# ArduinoUnoShield.net
KiCad netlist of a schematic drawn in Altium Designer
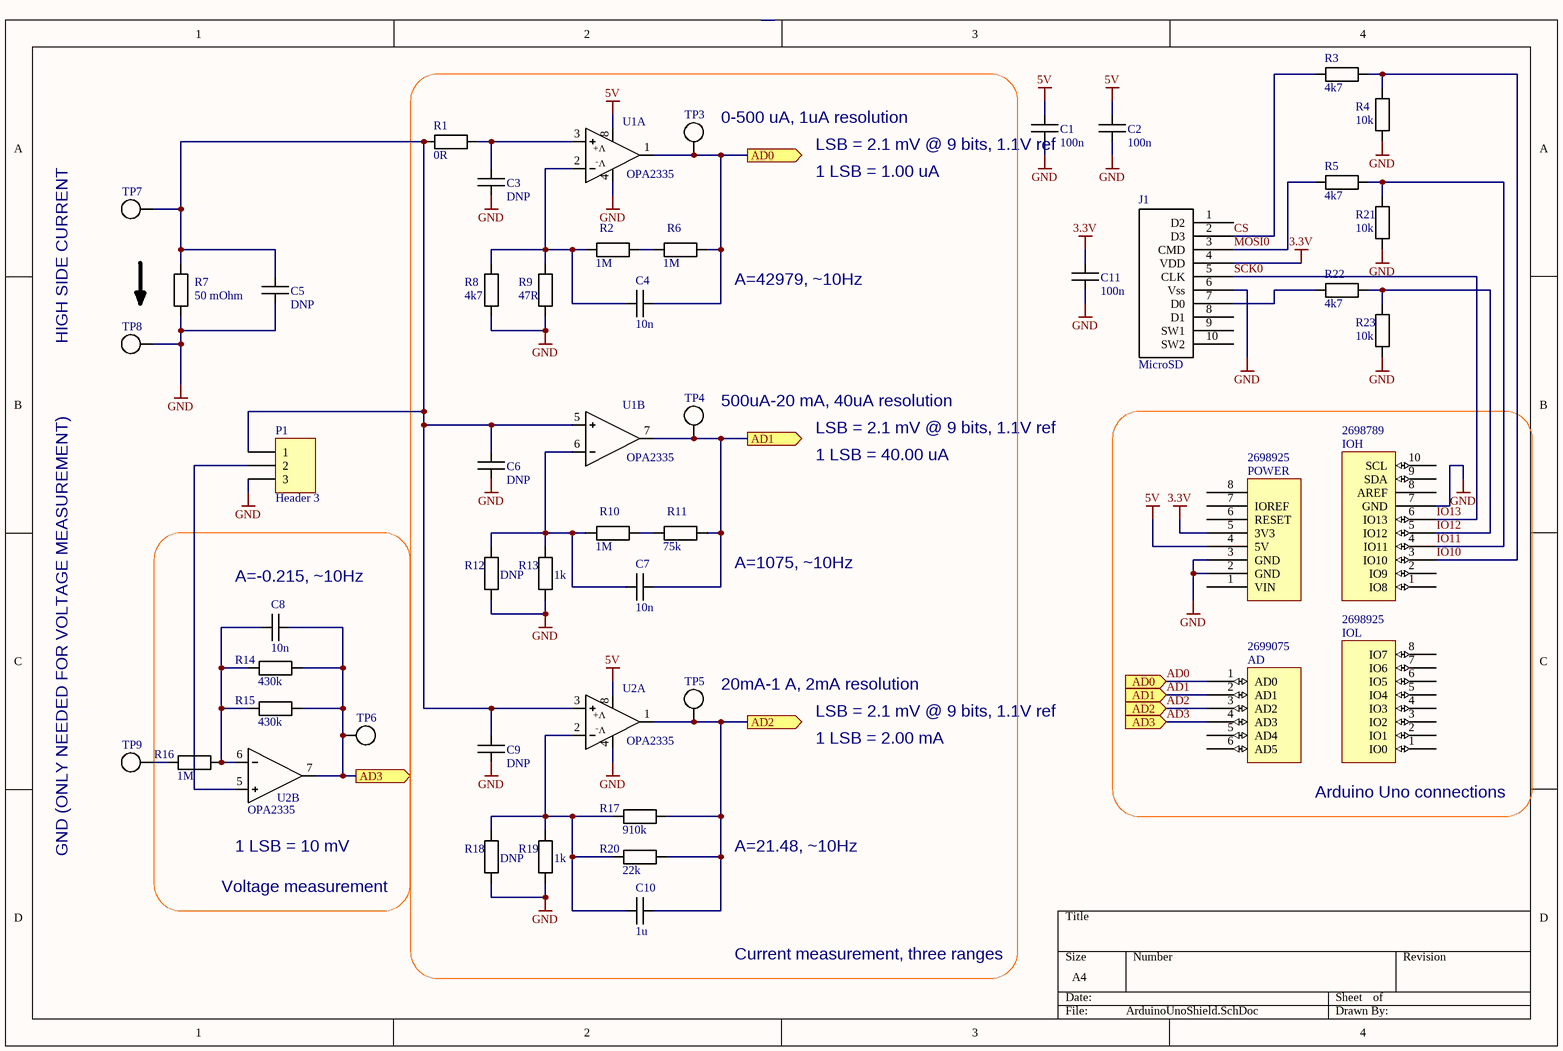
[diagram p0: ArduinoUnoShield.SchDoc]

(export (version "E")
  (design (tool "Eeschema 10.0.6"))
  (components
    (comp (ref "AD")
      (value "AD")
      (footprint "Header:Header 6x1 8.5mm")
      (fields (field (name "SUPPLIER PART NUMBER 4") "2699075"))
      (libsource (lib "Header") (part "AD"))
    )
    (comp (ref "C1")
      (value "100n")
      (footprint "0603CAP")
      (description "Ceramic Capacitor SMD 0603")
      (fields (field (name "Comment") "CAP0603"))
      (libsource (lib "PARTS") (part "185"))
    )
    (comp (ref "C2")
      (value "100n")
      (footprint "0603CAP")
      (description "Ceramic Capacitor SMD 0603")
      (fields (field (name "Comment") "CAP0603"))
      (libsource (lib "PARTS") (part "185"))
    )
    (comp (ref "C3")
      (value "DNP")
      (footprint "0603CAP")
      (description "Ceramic Capacitor SMD 0603")
      (fields (field (name "Comment") "CAP0603"))
      (libsource (lib "PARTS") (part "185"))
    )
    (comp (ref "C4")
      (value "10n")
      (footprint "0603CAP")
      (description "Ceramic Capacitor SMD 0603")
      (fields (field (name "Comment") "CAP0603"))
      (libsource (lib "PARTS") (part "185"))
    )
    (comp (ref "C5")
      (value "DNP")
      (footprint "0603CAP")
      (description "Ceramic Capacitor SMD 0603")
      (fields (field (name "Comment") "CAP0603"))
      (libsource (lib "PARTS") (part "185"))
    )
    (comp (ref "C6")
      (value "DNP")
      (footprint "0603CAP")
      (description "Ceramic Capacitor SMD 0603")
      (fields (field (name "Comment") "CAP0603"))
      (libsource (lib "PARTS") (part "185"))
    )
    (comp (ref "C7")
      (value "10n")
      (footprint "0603CAP")
      (description "Ceramic Capacitor SMD 0603")
      (fields (field (name "Comment") "CAP0603"))
      (libsource (lib "PARTS") (part "185"))
    )
    (comp (ref "C8")
      (value "10n")
      (footprint "0603CAP")
      (description "Ceramic Capacitor SMD 0603")
      (fields (field (name "Comment") "CAP0603"))
      (libsource (lib "PARTS") (part "185"))
    )
    (comp (ref "C9")
      (value "DNP")
      (footprint "0603CAP")
      (description "Ceramic Capacitor SMD 0603")
      (fields (field (name "Comment") "CAP0603"))
      (libsource (lib "PARTS") (part "185"))
    )
    (comp (ref "C10")
      (value "1u")
      (footprint "0603CAP")
      (description "Ceramic Capacitor SMD 0603")
      (fields (field (name "Comment") "CAP0603"))
      (libsource (lib "PARTS") (part "185"))
    )
    (comp (ref "C11")
      (value "100n")
      (footprint "0603CAP")
      (description "Ceramic Capacitor SMD 0603")
      (fields (field (name "Comment") "CAP0603"))
      (libsource (lib "PARTS") (part "185"))
    )
    (comp (ref "IOH")
      (value "IOH")
      (footprint "Header:Header 10x1 8.5mm")
      (fields (field (name "SUPPLIER PART NUMBER 3") "2698789"))
      (libsource (lib "Header") (part "IOH"))
    )
    (comp (ref "IOL")
      (value "IOL")
      (footprint "Header 8x1 8.5mm")
      (fields (field (name "SUPPLIER PART NUMBER 4") "2698925"))
      (libsource (lib "Header") (part "IOL"))
    )
    (comp (ref "J1") (value "MicroSD") (footprint "micro SD") (libsource (lib "moja") (part "MicroSD")))
    (comp (ref "P1")
      (value "Header 3")
      (footprint "HDR1X3")
      (description "Header, 3-Pin")
      (fields (field (name "PUBLISHER") "Altium Limited"))
      (libsource (lib "Miscellaneous Connectors") (part "Header 3"))
    )
    (comp (ref "POWER")
      (value "POWER_UNO")
      (footprint "Header 8x1 8.5mm")
      (fields (field (name "SUPPLIER PART NUMBER 4") "2698925"))
      (libsource (lib "Header") (part "POWER_UNO"))
    )
    (comp (ref "R1")
      (value "0R")
      (footprint "RES0603")
      (description "Resistor 0603 SMD")
      (fields (field (name "Comment") "RES_STANDARD"))
      (libsource (lib "PARTS") (part "276"))
    )
    (comp (ref "R2")
      (value "1M")
      (footprint "RES0603")
      (description "Resistor 0603 SMD")
      (fields (field (name "Comment") "RES_STANDARD"))
      (libsource (lib "PARTS") (part "276"))
    )
    (comp (ref "R3")
      (value "4k7")
      (footprint "RES0603")
      (description "Resistor 0603 SMD")
      (fields (field (name "Comment") "RES_STANDARD"))
      (libsource (lib "PARTS") (part "276"))
    )
    (comp (ref "R4")
      (value "10k")
      (footprint "RES0603")
      (description "Resistor 0603 SMD")
      (fields (field (name "Comment") "RES_STANDARD"))
      (libsource (lib "PARTS") (part "276"))
    )
    (comp (ref "R5")
      (value "4k7")
      (footprint "RES0603")
      (description "Resistor 0603 SMD")
      (fields (field (name "Comment") "RES_STANDARD"))
      (libsource (lib "PARTS") (part "276"))
    )
    (comp (ref "R6")
      (value "1M")
      (footprint "RES0603")
      (description "Resistor 0603 SMD")
      (fields (field (name "Comment") "RES_STANDARD"))
      (libsource (lib "PARTS") (part "276"))
    )
    (comp (ref "R7")
      (value "50 mOhm")
      (footprint "RES0603")
      (description "Resistor 0603 SMD")
      (fields (field (name "Comment") "RES_STANDARD"))
      (libsource (lib "PARTS") (part "276"))
    )
    (comp (ref "R8")
      (value "4k7")
      (footprint "RES0603")
      (description "Resistor 0603 SMD")
      (fields (field (name "Comment") "RES_STANDARD"))
      (libsource (lib "PARTS") (part "276"))
    )
    (comp (ref "R9")
      (value "47R")
      (footprint "RES0603")
      (description "Resistor 0603 SMD")
      (fields (field (name "Comment") "RES_STANDARD"))
      (libsource (lib "PARTS") (part "276"))
    )
    (comp (ref "R10")
      (value "1M")
      (footprint "RES0603")
      (description "Resistor 0603 SMD")
      (fields (field (name "Comment") "RES_STANDARD"))
      (libsource (lib "PARTS") (part "276"))
    )
    (comp (ref "R11")
      (value "75k")
      (footprint "RES0603")
      (description "Resistor 0603 SMD")
      (fields (field (name "Comment") "RES_STANDARD"))
      (libsource (lib "PARTS") (part "276"))
    )
    (comp (ref "R12")
      (value "DNP")
      (footprint "RES0603")
      (description "Resistor 0603 SMD")
      (fields (field (name "Comment") "RES_STANDARD"))
      (libsource (lib "PARTS") (part "276"))
    )
    (comp (ref "R13")
      (value "1k")
      (footprint "RES0603")
      (description "Resistor 0603 SMD")
      (fields (field (name "Comment") "RES_STANDARD"))
      (libsource (lib "PARTS") (part "276"))
    )
    (comp (ref "R14")
      (value "430k")
      (footprint "RES0603")
      (description "Resistor 0603 SMD")
      (fields (field (name "Comment") "RES_STANDARD"))
      (libsource (lib "PARTS") (part "276"))
    )
    (comp (ref "R15")
      (value "430k")
      (footprint "RES0603")
      (description "Resistor 0603 SMD")
      (fields (field (name "Comment") "RES_STANDARD"))
      (libsource (lib "PARTS") (part "276"))
    )
    (comp (ref "R16")
      (value "1M")
      (footprint "RES0603")
      (description "Resistor 0603 SMD")
      (fields (field (name "Comment") "RES_STANDARD"))
      (libsource (lib "PARTS") (part "276"))
    )
    (comp (ref "R17")
      (value "910k")
      (footprint "RES0603")
      (description "Resistor 0603 SMD")
      (fields (field (name "Comment") "RES_STANDARD"))
      (libsource (lib "PARTS") (part "276"))
    )
    (comp (ref "R18")
      (value "DNP")
      (footprint "RES0603")
      (description "Resistor 0603 SMD")
      (fields (field (name "Comment") "RES_STANDARD"))
      (libsource (lib "PARTS") (part "276"))
    )
    (comp (ref "R19")
      (value "1k")
      (footprint "RES0603")
      (description "Resistor 0603 SMD")
      (fields (field (name "Comment") "RES_STANDARD"))
      (libsource (lib "PARTS") (part "276"))
    )
    (comp (ref "R20")
      (value "22k")
      (footprint "RES0603")
      (description "Resistor 0603 SMD")
      (fields (field (name "Comment") "RES_STANDARD"))
      (libsource (lib "PARTS") (part "276"))
    )
    (comp (ref "R21")
      (value "10k")
      (footprint "RES0603")
      (description "Resistor 0603 SMD")
      (fields (field (name "Comment") "RES_STANDARD"))
      (libsource (lib "PARTS") (part "276"))
    )
    (comp (ref "R22")
      (value "4k7")
      (footprint "RES0603")
      (description "Resistor 0603 SMD")
      (fields (field (name "Comment") "RES_STANDARD"))
      (libsource (lib "PARTS") (part "276"))
    )
    (comp (ref "R23")
      (value "10k")
      (footprint "RES0603")
      (description "Resistor 0603 SMD")
      (fields (field (name "Comment") "RES_STANDARD"))
      (libsource (lib "PARTS") (part "276"))
    )
    (comp (ref "TP3")
      (value "TESTPOINT_1.6MM")
      (footprint "TESTPOINT_1.6MM")
      (description "Testpoint")
      (libsource (lib "PARTS") (part "203"))
    )
    (comp (ref "TP4")
      (value "TESTPOINT_1.6MM")
      (footprint "TESTPOINT_1.6MM")
      (description "Testpoint")
      (libsource (lib "PARTS") (part "203"))
    )
    (comp (ref "TP5")
      (value "TESTPOINT_1.6MM")
      (footprint "TESTPOINT_1.6MM")
      (description "Testpoint")
      (libsource (lib "PARTS") (part "203"))
    )
    (comp (ref "TP6")
      (value "TESTPOINT_1.6MM")
      (footprint "TESTPOINT_1.6MM")
      (description "Testpoint")
      (libsource (lib "PARTS") (part "203"))
    )
    (comp (ref "TP7")
      (value "TESTPOINT_1.6MM")
      (footprint "TESTPOINT_1.6MM")
      (description "Testpoint")
      (libsource (lib "PARTS") (part "203"))
    )
    (comp (ref "TP8")
      (value "TESTPOINT_1.6MM")
      (footprint "TESTPOINT_1.6MM")
      (description "Testpoint")
      (libsource (lib "PARTS") (part "203"))
    )
    (comp (ref "TP9")
      (value "TESTPOINT_1.6MM")
      (footprint "TESTPOINT_1.6MM")
      (description "Testpoint")
      (libsource (lib "PARTS") (part "203"))
    )
    (comp (ref "U1")
      (value "OPA2335")
      (footprint "SO8")
      (description "Dual and Quad 75 MHz GBW Rail-to-Rail I/O Operational")
      (libsource (lib "PARTS") (part "104"))
    )
    (comp (ref "U2")
      (value "OPA2335")
      (footprint "SO8")
      (description "Dual and Quad 75 MHz GBW Rail-to-Rail I/O Operational")
      (libsource (lib "PARTS") (part "104"))
    )
  )
  (nets
    (net (code "1") (name "/AD0") (class "Default")
      (node (ref "AD") (pin "1") (pinfunction "AD0_1") (pintype "bidirectional"))
      (node (ref "C4") (pin "2") (pinfunction "2_2") (pintype "passive"))
      (node (ref "R6") (pin "1") (pinfunction "1_1") (pintype "passive"))
      (node (ref "TP3") (pin "1") (pinfunction "1_1") (pintype "passive"))
      (node (ref "U1") (pin "1") (pinfunction "Output_A_1") (pintype "passive"))
    )
    (net (code "2") (name "/AD1") (class "Default")
      (node (ref "AD") (pin "2") (pinfunction "AD1_2") (pintype "bidirectional"))
      (node (ref "C7") (pin "2") (pinfunction "2_2") (pintype "passive"))
      (node (ref "R11") (pin "1") (pinfunction "1_1") (pintype "passive"))
      (node (ref "TP4") (pin "1") (pinfunction "1_1") (pintype "passive"))
      (node (ref "U1") (pin "7") (pinfunction "OUT_B_7") (pintype "passive"))
    )
    (net (code "3") (name "/AD2") (class "Default")
      (node (ref "AD") (pin "3") (pinfunction "AD2_3") (pintype "bidirectional"))
      (node (ref "C10") (pin "2") (pinfunction "2_2") (pintype "passive"))
      (node (ref "R17") (pin "1") (pinfunction "1_1") (pintype "passive"))
      (node (ref "R20") (pin "1") (pinfunction "1_1") (pintype "passive"))
      (node (ref "TP5") (pin "1") (pinfunction "1_1") (pintype "passive"))
      (node (ref "U2") (pin "1") (pinfunction "Output_A_1") (pintype "passive"))
    )
    (net (code "4") (name "/AD3") (class "Default")
      (node (ref "AD") (pin "4") (pinfunction "AD3_4") (pintype "bidirectional"))
      (node (ref "C8") (pin "2") (pinfunction "2_2") (pintype "passive"))
      (node (ref "R14") (pin "1") (pinfunction "1_1") (pintype "passive"))
      (node (ref "R15") (pin "1") (pinfunction "1_1") (pintype "passive"))
      (node (ref "TP6") (pin "1") (pinfunction "1_1") (pintype "passive"))
      (node (ref "U2") (pin "7") (pinfunction "OUT_B_7") (pintype "passive"))
    )
    (net (code "5") (name "/CS") (class "Default")
      (node (ref "J1") (pin "2") (pinfunction "D3_2") (pintype "passive"))
      (node (ref "R3") (pin "2") (pinfunction "2_2") (pintype "passive"))
    )
    (net (code "6") (name "/IO10") (class "Default")
      (node (ref "IOH") (pin "3") (pinfunction "IO10_3") (pintype "bidirectional"))
      (node (ref "R3") (pin "1") (pinfunction "1_1") (pintype "passive"))
      (node (ref "R4") (pin "2") (pinfunction "2_2") (pintype "passive"))
    )
    (net (code "7") (name "/IO11") (class "Default")
      (node (ref "IOH") (pin "4") (pinfunction "IO11_4") (pintype "bidirectional"))
      (node (ref "R21") (pin "2") (pinfunction "2_2") (pintype "passive"))
      (node (ref "R5") (pin "1") (pinfunction "1_1") (pintype "passive"))
    )
    (net (code "8") (name "/IO12") (class "Default")
      (node (ref "IOH") (pin "5") (pinfunction "IO12_5") (pintype "bidirectional"))
      (node (ref "R22") (pin "1") (pinfunction "1_1") (pintype "passive"))
      (node (ref "R23") (pin "2") (pinfunction "2_2") (pintype "passive"))
    )
    (net (code "9") (name "/IO13") (class "Default")
      (node (ref "IOH") (pin "6") (pinfunction "IO13_6") (pintype "bidirectional"))
      (node (ref "J1") (pin "5") (pinfunction "CLK_5") (pintype "passive"))
    )
    (net (code "10") (name "/MOSI0") (class "Default")
      (node (ref "J1") (pin "3") (pinfunction "CMD_3") (pintype "passive"))
      (node (ref "R5") (pin "2") (pinfunction "2_2") (pintype "passive"))
    )
    (net (code "11") (name "3.3V") (class "Default")
      (node (ref "C11") (pin "2") (pinfunction "2_2") (pintype "passive"))
      (node (ref "J1") (pin "4") (pinfunction "VDD_4") (pintype "passive"))
      (node (ref "POWER") (pin "5") (pinfunction "3V3_5") (pintype "power_in"))
    )
    (net (code "12") (name "5V") (class "Default")
      (node (ref "C1") (pin "2") (pinfunction "2_2") (pintype "passive"))
      (node (ref "C2") (pin "2") (pinfunction "2_2") (pintype "passive"))
      (node (ref "POWER") (pin "4") (pinfunction "5V_4") (pintype "power_in"))
      (node (ref "U1") (pin "8") (pinfunction "V+_8") (pintype "passive"))
      (node (ref "U2") (pin "8") (pinfunction "V+_8") (pintype "passive"))
    )
    (net (code "13") (name "GND") (class "Default")
      (node (ref "C1") (pin "1") (pinfunction "1_1") (pintype "passive"))
      (node (ref "C11") (pin "1") (pinfunction "1_1") (pintype "passive"))
      (node (ref "C2") (pin "1") (pinfunction "1_1") (pintype "passive"))
      (node (ref "C3") (pin "2") (pinfunction "2_2") (pintype "passive"))
      (node (ref "C5") (pin "2") (pinfunction "2_2") (pintype "passive"))
      (node (ref "C6") (pin "2") (pinfunction "2_2") (pintype "passive"))
      (node (ref "C9") (pin "2") (pinfunction "2_2") (pintype "passive"))
      (node (ref "IOH") (pin "7") (pinfunction "GND_7") (pintype "power_in"))
      (node (ref "J1") (pin "6") (pinfunction "Vss_6") (pintype "passive"))
      (node (ref "P1") (pin "3") (pinfunction "3_3") (pintype "passive"))
      (node (ref "POWER") (pin "2") (pinfunction "GND_2") (pintype "power_in"))
      (node (ref "POWER") (pin "3") (pinfunction "GND_3") (pintype "power_in"))
      (node (ref "R12") (pin "1") (pinfunction "1_1") (pintype "passive"))
      (node (ref "R13") (pin "1") (pinfunction "1_1") (pintype "passive"))
      (node (ref "R18") (pin "1") (pinfunction "1_1") (pintype "passive"))
      (node (ref "R19") (pin "1") (pinfunction "1_1") (pintype "passive"))
      (node (ref "R21") (pin "1") (pinfunction "1_1") (pintype "passive"))
      (node (ref "R23") (pin "1") (pinfunction "1_1") (pintype "passive"))
      (node (ref "R4") (pin "1") (pinfunction "1_1") (pintype "passive"))
      (node (ref "R7") (pin "1") (pinfunction "1_1") (pintype "passive"))
      (node (ref "R8") (pin "1") (pinfunction "1_1") (pintype "passive"))
      (node (ref "R9") (pin "1") (pinfunction "1_1") (pintype "passive"))
      (node (ref "TP8") (pin "1") (pinfunction "1_1") (pintype "passive"))
      (node (ref "U1") (pin "4") (pinfunction "V-_4") (pintype "passive"))
      (node (ref "U2") (pin "4") (pinfunction "V-_4") (pintype "passive"))
    )
    (net (code "14") (name "Net-(J1-D0)") (class "Default")
      (node (ref "J1") (pin "7") (pinfunction "D0_7") (pintype "passive"))
      (node (ref "R22") (pin "2") (pinfunction "2_2") (pintype "passive"))
    )
    (net (code "15") (name "Net-(R2-Pad1)") (class "Default")
      (node (ref "R2") (pin "1") (pinfunction "1_1") (pintype "passive"))
      (node (ref "R6") (pin "2") (pinfunction "2_2") (pintype "passive"))
    )
    (net (code "16") (name "Net-(R10-Pad1)") (class "Default")
      (node (ref "R10") (pin "1") (pinfunction "1_1") (pintype "passive"))
      (node (ref "R11") (pin "2") (pinfunction "2_2") (pintype "passive"))
    )
    (net (code "17") (name "Net-(R16-Pad2)") (class "Default")
      (node (ref "R16") (pin "2") (pinfunction "2_2") (pintype "passive"))
      (node (ref "TP9") (pin "1") (pinfunction "1_1") (pintype "passive"))
    )
    (net (code "18") (name "Net-(U1A-Inv_IN_A)") (class "Default")
      (node (ref "C4") (pin "1") (pinfunction "1_1") (pintype "passive"))
      (node (ref "R2") (pin "2") (pinfunction "2_2") (pintype "passive"))
      (node (ref "R8") (pin "2") (pinfunction "2_2") (pintype "passive"))
      (node (ref "R9") (pin "2") (pinfunction "2_2") (pintype "passive"))
      (node (ref "U1") (pin "2") (pinfunction "Inv_IN_A_2") (pintype "passive"))
    )
    (net (code "19") (name "Net-(U1A-Non-inv_IN_A)") (class "Default")
      (node (ref "C3") (pin "1") (pinfunction "1_1") (pintype "passive"))
      (node (ref "R1") (pin "2") (pinfunction "2_2") (pintype "passive"))
      (node (ref "U1") (pin "3") (pinfunction "Non-inv_IN_A_3") (pintype "passive"))
    )
    (net (code "20") (name "Net-(U1B-Inv_IN_B)") (class "Default")
      (node (ref "C7") (pin "1") (pinfunction "1_1") (pintype "passive"))
      (node (ref "R10") (pin "2") (pinfunction "2_2") (pintype "passive"))
      (node (ref "R12") (pin "2") (pinfunction "2_2") (pintype "passive"))
      (node (ref "R13") (pin "2") (pinfunction "2_2") (pintype "passive"))
      (node (ref "U1") (pin "6") (pinfunction "Inv_IN_B_6") (pintype "passive"))
    )
    (net (code "21") (name "Net-(U1B-Non-inv_IN_B)") (class "Default")
      (node (ref "C5") (pin "1") (pinfunction "1_1") (pintype "passive"))
      (node (ref "C6") (pin "1") (pinfunction "1_1") (pintype "passive"))
      (node (ref "C9") (pin "1") (pinfunction "1_1") (pintype "passive"))
      (node (ref "P1") (pin "1") (pinfunction "1_1") (pintype "passive"))
      (node (ref "R1") (pin "1") (pinfunction "1_1") (pintype "passive"))
      (node (ref "R7") (pin "2") (pinfunction "2_2") (pintype "passive"))
      (node (ref "TP7") (pin "1") (pinfunction "1_1") (pintype "passive"))
      (node (ref "U1") (pin "5") (pinfunction "Non-inv_IN_B_5") (pintype "passive"))
      (node (ref "U2") (pin "3") (pinfunction "Non-inv_IN_A_3") (pintype "passive"))
    )
    (net (code "22") (name "Net-(U2A-Inv_IN_A)") (class "Default")
      (node (ref "C10") (pin "1") (pinfunction "1_1") (pintype "passive"))
      (node (ref "R17") (pin "2") (pinfunction "2_2") (pintype "passive"))
      (node (ref "R18") (pin "2") (pinfunction "2_2") (pintype "passive"))
      (node (ref "R19") (pin "2") (pinfunction "2_2") (pintype "passive"))
      (node (ref "R20") (pin "2") (pinfunction "2_2") (pintype "passive"))
      (node (ref "U2") (pin "2") (pinfunction "Inv_IN_A_2") (pintype "passive"))
    )
    (net (code "23") (name "Net-(U2B-Inv_IN_B)") (class "Default")
      (node (ref "C8") (pin "1") (pinfunction "1_1") (pintype "passive"))
      (node (ref "R14") (pin "2") (pinfunction "2_2") (pintype "passive"))
      (node (ref "R15") (pin "2") (pinfunction "2_2") (pintype "passive"))
      (node (ref "R16") (pin "1") (pinfunction "1_1") (pintype "passive"))
      (node (ref "U2") (pin "6") (pinfunction "Inv_IN_B_6") (pintype "passive"))
    )
    (net (code "24") (name "Net-(U2B-Non-inv_IN_B)") (class "Default")
      (node (ref "P1") (pin "2") (pinfunction "2_2") (pintype "passive"))
      (node (ref "U2") (pin "5") (pinfunction "Non-inv_IN_B_5") (pintype "passive"))
    )
    (net (code "25") (name "unconnected-(AD-AD4-Pad5)") (class "Default")
      (node (ref "AD") (pin "5") (pinfunction "AD4_5") (pintype "bidirectional"))
    )
    (net (code "26") (name "unconnected-(AD-AD5-Pad6)") (class "Default")
      (node (ref "AD") (pin "6") (pinfunction "AD5_6") (pintype "bidirectional"))
    )
    (net (code "27") (name "unconnected-(IOH-AREF-Pad8)") (class "Default")
      (node (ref "IOH") (pin "8") (pinfunction "AREF_8") (pintype "passive"))
    )
    (net (code "28") (name "unconnected-(IOH-IO8-Pad1)") (class "Default")
      (node (ref "IOH") (pin "1") (pinfunction "IO8_1") (pintype "bidirectional"))
    )
    (net (code "29") (name "unconnected-(IOH-IO9-Pad2)") (class "Default")
      (node (ref "IOH") (pin "2") (pinfunction "IO9_2") (pintype "bidirectional"))
    )
    (net (code "30") (name "unconnected-(IOH-SCL-Pad10)") (class "Default")
      (node (ref "IOH") (pin "10") (pinfunction "SCL_10") (pintype "bidirectional"))
    )
    (net (code "31") (name "unconnected-(IOH-SDA-Pad9)") (class "Default")
      (node (ref "IOH") (pin "9") (pinfunction "SDA_9") (pintype "bidirectional"))
    )
    (net (code "32") (name "unconnected-(IOL-IO0-Pad1)") (class "Default")
      (node (ref "IOL") (pin "1") (pinfunction "IO0_1") (pintype "bidirectional"))
    )
    (net (code "33") (name "unconnected-(IOL-IO1-Pad2)") (class "Default")
      (node (ref "IOL") (pin "2") (pinfunction "IO1_2") (pintype "bidirectional"))
    )
    (net (code "34") (name "unconnected-(IOL-IO2-Pad3)") (class "Default")
      (node (ref "IOL") (pin "3") (pinfunction "IO2_3") (pintype "bidirectional"))
    )
    (net (code "35") (name "unconnected-(IOL-IO3-Pad4)") (class "Default")
      (node (ref "IOL") (pin "4") (pinfunction "IO3_4") (pintype "bidirectional"))
    )
    (net (code "36") (name "unconnected-(IOL-IO4-Pad5)") (class "Default")
      (node (ref "IOL") (pin "5") (pinfunction "IO4_5") (pintype "bidirectional"))
    )
    (net (code "37") (name "unconnected-(IOL-IO5-Pad6)") (class "Default")
      (node (ref "IOL") (pin "6") (pinfunction "IO5_6") (pintype "bidirectional"))
    )
    (net (code "38") (name "unconnected-(IOL-IO6-Pad7)") (class "Default")
      (node (ref "IOL") (pin "7") (pinfunction "IO6_7") (pintype "bidirectional"))
    )
    (net (code "39") (name "unconnected-(IOL-IO7-Pad8)") (class "Default")
      (node (ref "IOL") (pin "8") (pinfunction "IO7_8") (pintype "bidirectional"))
    )
    (net (code "40") (name "unconnected-(J1-D1-Pad8)") (class "Default")
      (node (ref "J1") (pin "8") (pinfunction "D1_8") (pintype "passive"))
    )
    (net (code "41") (name "unconnected-(J1-D2-Pad1)") (class "Default")
      (node (ref "J1") (pin "1") (pinfunction "D2_1") (pintype "passive"))
    )
    (net (code "42") (name "unconnected-(J1-SW1-Pad9)") (class "Default")
      (node (ref "J1") (pin "9") (pinfunction "SW1_9") (pintype "passive"))
    )
    (net (code "43") (name "unconnected-(J1-SW2-Pad10)") (class "Default")
      (node (ref "J1") (pin "10") (pinfunction "SW2_10") (pintype "passive"))
    )
    (net (code "44") (name "unconnected-(POWER-IOREF-Pad7)") (class "Default")
      (node (ref "POWER") (pin "7") (pinfunction "IOREF_7") (pintype "power_in"))
    )
    (net (code "45") (name "unconnected-(POWER-Pad8)") (class "Default")
      (node (ref "POWER") (pin "8") (pintype "passive"))
    )
    (net (code "46") (name "unconnected-(POWER-RESET-Pad6)") (class "Default")
      (node (ref "POWER") (pin "6") (pinfunction "RESET_6") (pintype "passive"))
    )
    (net (code "47") (name "unconnected-(POWER-VIN-Pad1)") (class "Default")
      (node (ref "POWER") (pin "1") (pinfunction "VIN_1") (pintype "power_in"))
    )
  )
)
